# DiffProbe.net
KiCad netlist of a schematic drawn in EAGLE
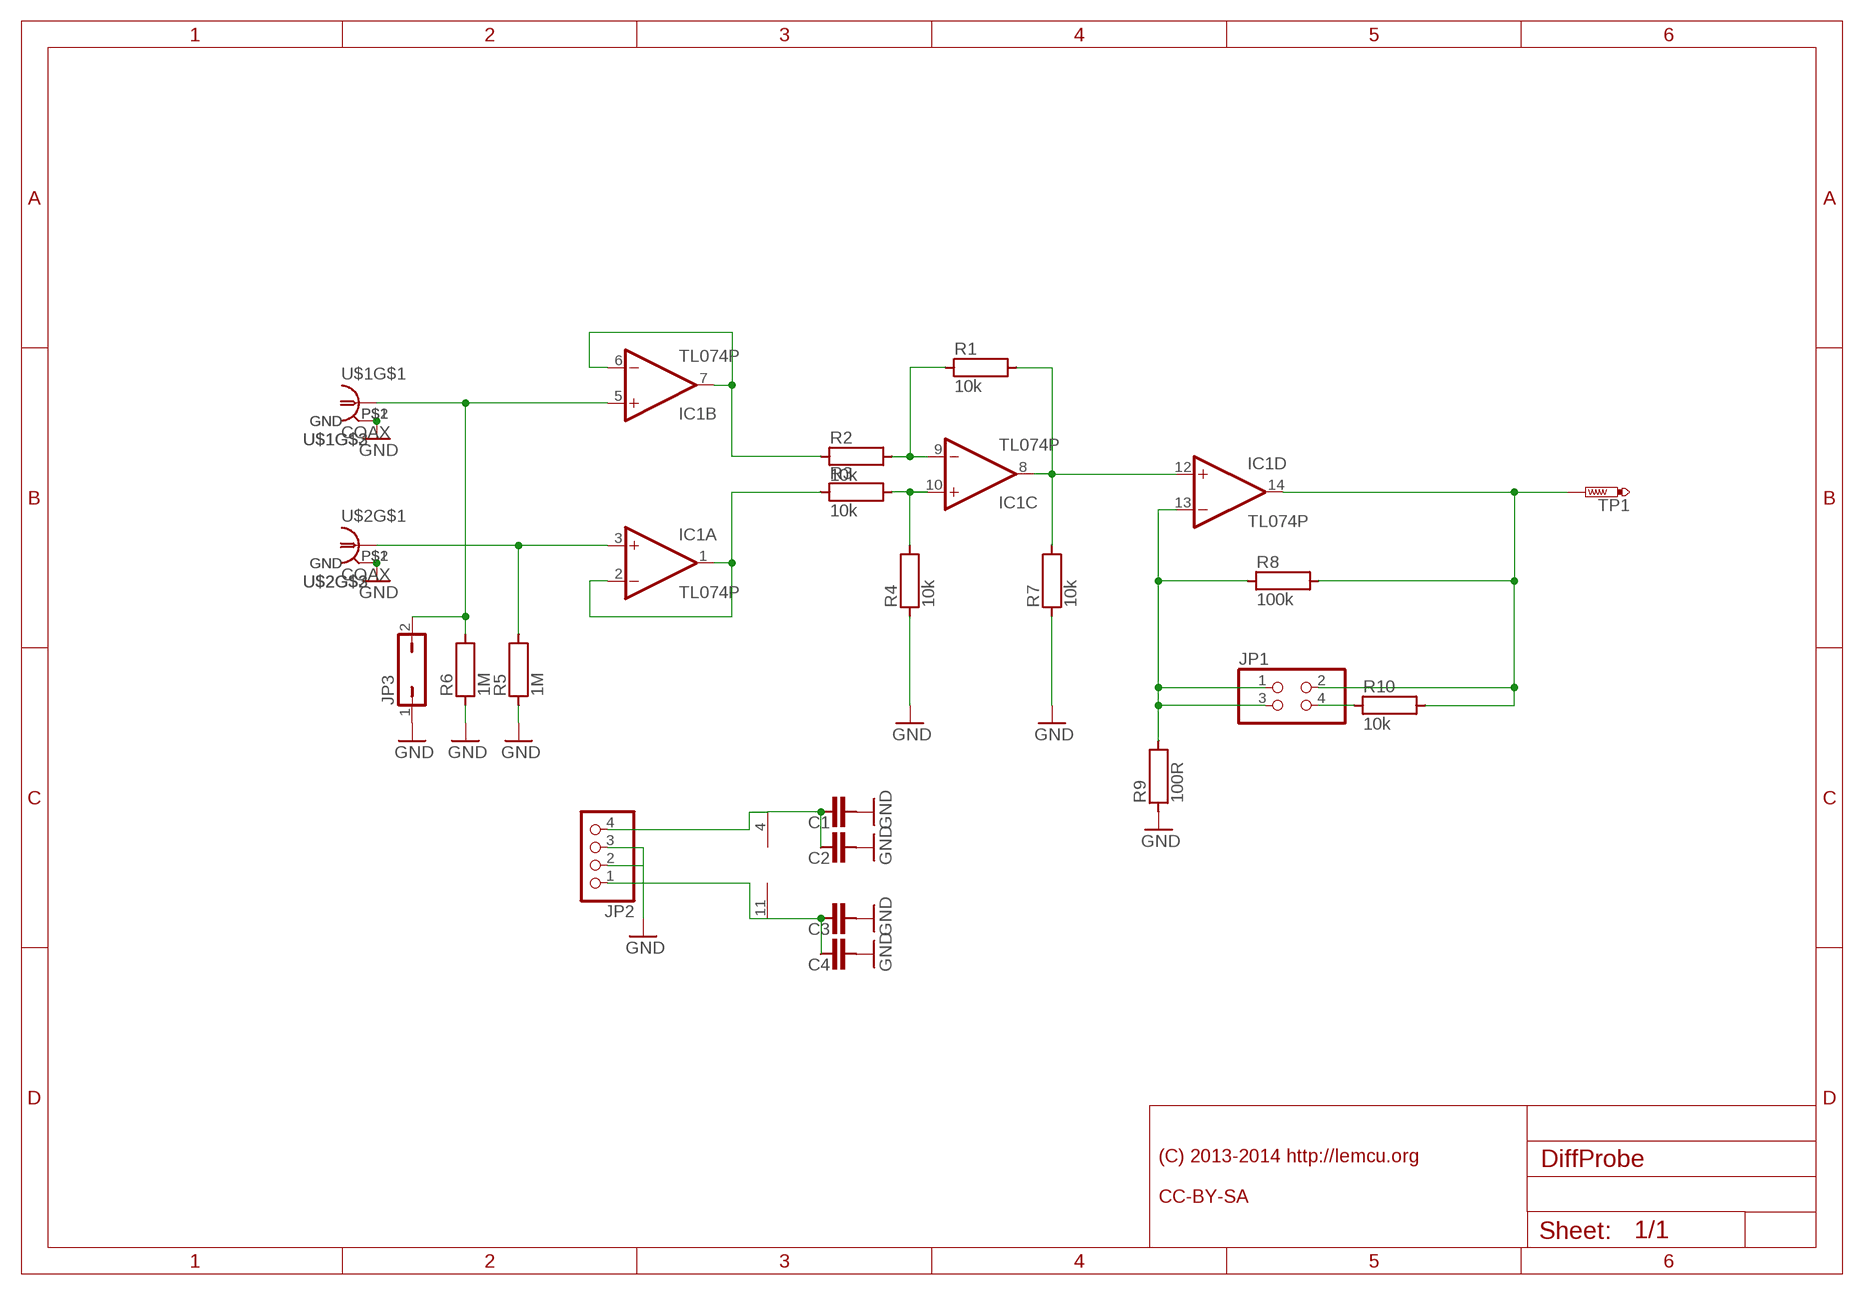
[diagram p0: schematic, sheet 1]

(export (version "E")
  (design (tool "Eeschema 10.0.6"))
  (components
    (comp (ref "C1")
      (value "C0603")
      (footprint "eagle-import:C0603")
      (libsource (lib "eagle-import") (part "C0603"))
    )
    (comp (ref "C2")
      (value "C1206")
      (footprint "eagle-import:C1206")
      (libsource (lib "eagle-import") (part "C1206"))
    )
    (comp (ref "C3")
      (value "C0603")
      (footprint "eagle-import:C0603")
      (libsource (lib "eagle-import") (part "C0603"))
    )
    (comp (ref "C4")
      (value "C1206")
      (footprint "eagle-import:C1206")
      (libsource (lib "eagle-import") (part "C1206"))
    )
    (comp (ref "IC1")
      (value "TL074P")
      (footprint "eagle-import:DIL14")
      (libsource (lib "eagle-import") (part "TL074P"))
    )
    (comp (ref "JP1")
      (value "PINHD-2X2")
      (footprint "eagle-import:2X02")
      (libsource (lib "eagle-import") (part "PINHD-2X2"))
    )
    (comp (ref "JP2")
      (value "PINHD-1X4")
      (footprint "eagle-import:1X04")
      (libsource (lib "eagle-import") (part "PINHD-1X4"))
    )
    (comp (ref "JP3")
      (value "JP1Q")
      (footprint "eagle-import:JP1")
      (libsource (lib "eagle-import") (part "JP1Q"))
    )
    (comp (ref "R1")
      (value "10k")
      (footprint "eagle-import:R0603")
      (libsource (lib "eagle-import") (part "R0603"))
    )
    (comp (ref "R2")
      (value "10k")
      (footprint "eagle-import:R0603")
      (libsource (lib "eagle-import") (part "R0603"))
    )
    (comp (ref "R3")
      (value "10k")
      (footprint "eagle-import:R0603")
      (libsource (lib "eagle-import") (part "R0603"))
    )
    (comp (ref "R4")
      (value "10k")
      (footprint "eagle-import:R0603")
      (libsource (lib "eagle-import") (part "R0603"))
    )
    (comp (ref "R5")
      (value "1M")
      (footprint "eagle-import:R0603")
      (libsource (lib "eagle-import") (part "R0603"))
    )
    (comp (ref "R6")
      (value "1M")
      (footprint "eagle-import:R0603")
      (libsource (lib "eagle-import") (part "R0603"))
    )
    (comp (ref "R7")
      (value "10k")
      (footprint "eagle-import:R0603")
      (libsource (lib "eagle-import") (part "R0603"))
    )
    (comp (ref "R8")
      (value "100k")
      (footprint "eagle-import:R0603")
      (libsource (lib "eagle-import") (part "R0603"))
    )
    (comp (ref "R9")
      (value "100R")
      (footprint "eagle-import:R0603")
      (libsource (lib "eagle-import") (part "R0603"))
    )
    (comp (ref "R10")
      (value "10k")
      (footprint "eagle-import:R0603")
      (libsource (lib "eagle-import") (part "R0603"))
    )
    (comp (ref "TP1")
      (value "PTR1B1,27")
      (footprint "eagle-import:B1,27")
      (libsource (lib "eagle-import") (part "PTR1B1,27"))
    )
    (comp (ref "U$1")
      (value "COAX")
      (footprint "eagle-import:COAX_GND")
      (libsource (lib "eagle-import") (part "COAX"))
    )
    (comp (ref "U$2")
      (value "COAX")
      (footprint "eagle-import:COAX_GND")
      (libsource (lib "eagle-import") (part "COAX"))
    )
  )
  (nets
    (net (code "1") (name "GND") (class "Default")
      (node (ref "C1") (pin "1") (pinfunction "1_1") (pintype "passive"))
      (node (ref "C2") (pin "1") (pinfunction "1_1") (pintype "passive"))
      (node (ref "C3") (pin "1") (pinfunction "1_1") (pintype "passive"))
      (node (ref "C4") (pin "1") (pinfunction "1_1") (pintype "passive"))
      (node (ref "JP2") (pin "2") (pinfunction "2_2") (pintype "passive"))
      (node (ref "JP2") (pin "3") (pinfunction "3_3") (pintype "passive"))
      (node (ref "JP3") (pin "1") (pinfunction "1_1") (pintype "passive"))
      (node (ref "R4") (pin "1") (pinfunction "1_1") (pintype "passive"))
      (node (ref "R5") (pin "1") (pinfunction "1_1") (pintype "passive"))
      (node (ref "R6") (pin "1") (pinfunction "1_1") (pintype "passive"))
      (node (ref "R7") (pin "1") (pinfunction "1_1") (pintype "passive"))
      (node (ref "R9") (pin "1") (pinfunction "1_1") (pintype "passive"))
      (node (ref "U$1") (pin "4") (pinfunction "GND_4") (pintype "power_in"))
      (node (ref "U$1") (pin "P$1") (pinfunction "GND_P$1") (pintype "power_in"))
      (node (ref "U$1") (pin "P$2") (pinfunction "GND_P$2") (pintype "power_in"))
      (node (ref "U$2") (pin "4") (pinfunction "GND_4") (pintype "power_in"))
      (node (ref "U$2") (pin "P$1") (pinfunction "GND_P$1") (pintype "power_in"))
      (node (ref "U$2") (pin "P$2") (pinfunction "GND_P$2") (pintype "power_in"))
    )
    (net (code "2") (name "Net-(IC1A-+IN)") (class "Default")
      (node (ref "IC1") (pin "3") (pinfunction "+IN_3") (pintype "input"))
      (node (ref "R5") (pin "2") (pinfunction "2_2") (pintype "passive"))
      (node (ref "U$2") (pin "3") (pinfunction "1_3") (pintype "passive"))
    )
    (net (code "3") (name "Net-(IC1A--IN)") (class "Default")
      (node (ref "IC1") (pin "1") (pinfunction "OUT_1") (pintype "output"))
      (node (ref "IC1") (pin "2") (pinfunction "-IN_2") (pintype "input"))
      (node (ref "R3") (pin "1") (pinfunction "1_1") (pintype "passive"))
    )
    (net (code "4") (name "Net-(IC1B-+IN)") (class "Default")
      (node (ref "IC1") (pin "5") (pinfunction "+IN_5") (pintype "input"))
      (node (ref "JP3") (pin "2") (pinfunction "2_2") (pintype "passive"))
      (node (ref "R6") (pin "2") (pinfunction "2_2") (pintype "passive"))
      (node (ref "U$1") (pin "3") (pinfunction "1_3") (pintype "passive"))
    )
    (net (code "5") (name "Net-(IC1B--IN)") (class "Default")
      (node (ref "IC1") (pin "6") (pinfunction "-IN_6") (pintype "input"))
      (node (ref "IC1") (pin "7") (pinfunction "OUT_7") (pintype "output"))
      (node (ref "R2") (pin "1") (pinfunction "1_1") (pintype "passive"))
    )
    (net (code "6") (name "Net-(IC1C-+IN)") (class "Default")
      (node (ref "IC1") (pin "10") (pinfunction "+IN_10") (pintype "input"))
      (node (ref "R3") (pin "2") (pinfunction "2_2") (pintype "passive"))
      (node (ref "R4") (pin "2") (pinfunction "2_2") (pintype "passive"))
    )
    (net (code "7") (name "Net-(IC1C--IN)") (class "Default")
      (node (ref "IC1") (pin "9") (pinfunction "-IN_9") (pintype "input"))
      (node (ref "R1") (pin "1") (pinfunction "1_1") (pintype "passive"))
      (node (ref "R2") (pin "2") (pinfunction "2_2") (pintype "passive"))
    )
    (net (code "8") (name "Net-(IC1C-OUT)") (class "Default")
      (node (ref "IC1") (pin "12") (pinfunction "+IN_12") (pintype "input"))
      (node (ref "IC1") (pin "8") (pinfunction "OUT_8") (pintype "output"))
      (node (ref "R1") (pin "2") (pinfunction "2_2") (pintype "passive"))
      (node (ref "R7") (pin "2") (pinfunction "2_2") (pintype "passive"))
    )
    (net (code "9") (name "Net-(IC1D--IN)") (class "Default")
      (node (ref "IC1") (pin "13") (pinfunction "-IN_13") (pintype "input"))
      (node (ref "JP1") (pin "1") (pinfunction "1_1") (pintype "passive"))
      (node (ref "JP1") (pin "3") (pinfunction "3_3") (pintype "passive"))
      (node (ref "R8") (pin "1") (pinfunction "1_1") (pintype "passive"))
      (node (ref "R9") (pin "2") (pinfunction "2_2") (pintype "passive"))
    )
    (net (code "10") (name "Net-(IC1D-OUT)") (class "Default")
      (node (ref "IC1") (pin "14") (pinfunction "OUT_14") (pintype "output"))
      (node (ref "JP1") (pin "2") (pinfunction "2_2") (pintype "passive"))
      (node (ref "R10") (pin "2") (pinfunction "2_2") (pintype "passive"))
      (node (ref "R8") (pin "2") (pinfunction "2_2") (pintype "passive"))
      (node (ref "TP1") (pin "TP") (pinfunction "TP_TP") (pintype "input"))
    )
    (net (code "11") (name "Net-(IC1E-V+)") (class "Default")
      (node (ref "C1") (pin "2") (pinfunction "2_2") (pintype "passive"))
      (node (ref "C2") (pin "2") (pinfunction "2_2") (pintype "passive"))
      (node (ref "IC1") (pin "4") (pinfunction "V+_4") (pintype "power_in"))
      (node (ref "JP2") (pin "4") (pinfunction "4_4") (pintype "passive"))
    )
    (net (code "12") (name "Net-(IC1E-V-)") (class "Default")
      (node (ref "C3") (pin "2") (pinfunction "2_2") (pintype "passive"))
      (node (ref "C4") (pin "2") (pinfunction "2_2") (pintype "passive"))
      (node (ref "IC1") (pin "11") (pinfunction "V-_11") (pintype "power_in"))
      (node (ref "JP2") (pin "1") (pinfunction "1_1") (pintype "passive"))
    )
    (net (code "13") (name "Net-(JP1-Pad4)") (class "Default")
      (node (ref "JP1") (pin "4") (pinfunction "4_4") (pintype "passive"))
      (node (ref "R10") (pin "1") (pinfunction "1_1") (pintype "passive"))
    )
  )
)
